# board.net
KiCad netlist of a schematic drawn in EAGLE
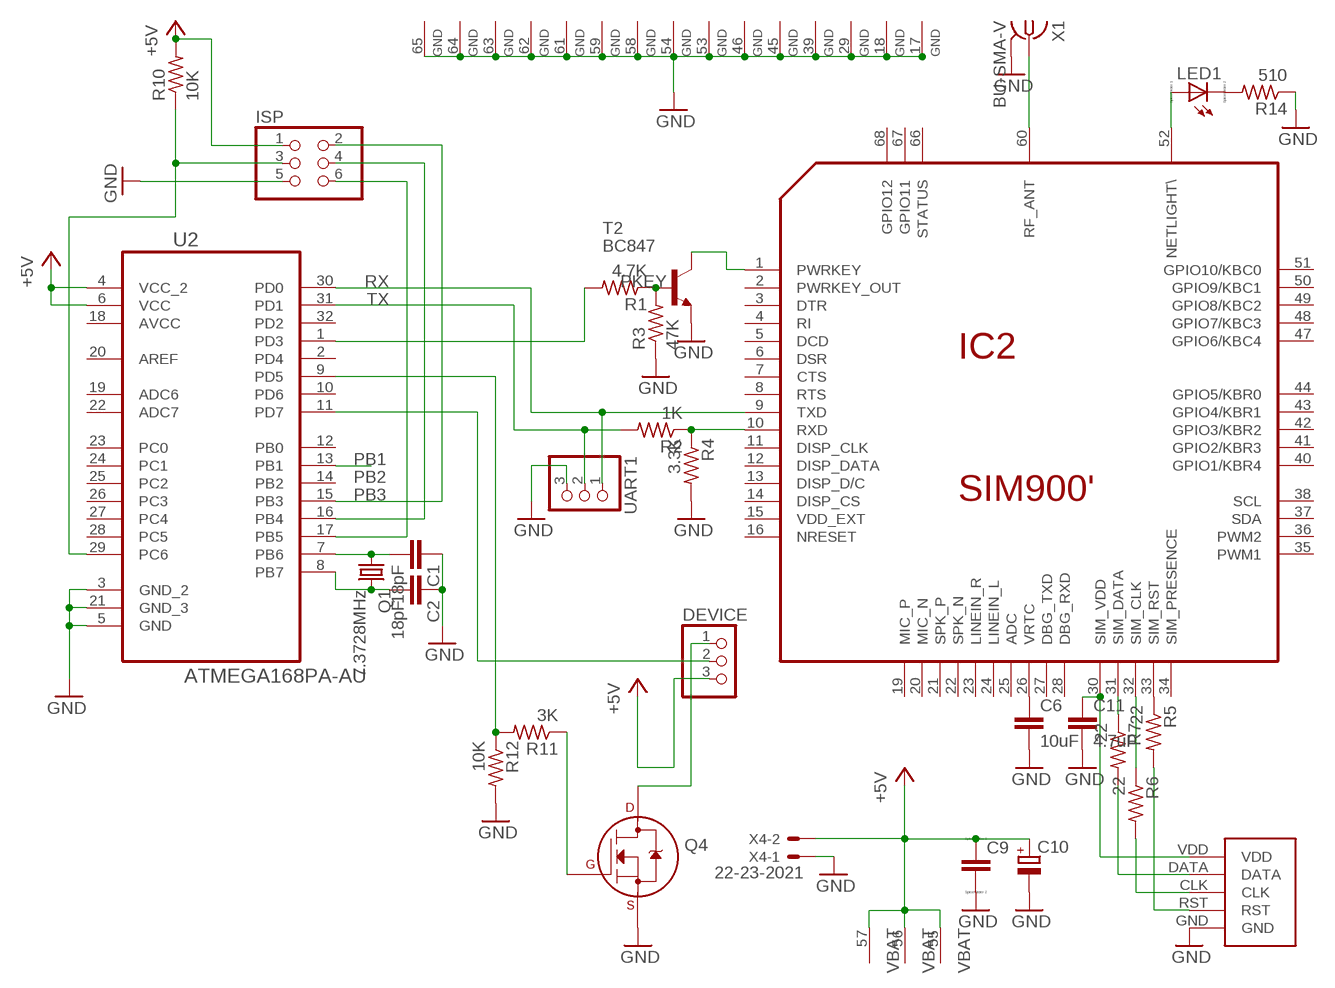
[diagram p0: schematic, sheet 1]

(export (version "E")
  (design (tool "Eeschema 10.0.6"))
  (components
    (comp (ref "C1")
      (value "18pF")
      (footprint "eagle-import:C1206")
      (libsource (lib "eagle-import") (part "C-EUC1206"))
    )
    (comp (ref "C2")
      (value "18pF")
      (footprint "eagle-import:C1206")
      (libsource (lib "eagle-import") (part "C-EUC1206"))
    )
    (comp (ref "C6")
      (value "10uF")
      (footprint "eagle-import:C1206")
      (libsource (lib "eagle-import") (part "C-EUC1206"))
    )
    (comp (ref "C9")
      (value "C-EUC1206K")
      (footprint "eagle-import:C1206K")
      (libsource (lib "eagle-import") (part "resistor_C-EUC1206K"))
    )
    (comp (ref "C10")
      (value "CPOL-EUE5-8.5")
      (footprint "eagle-import:E5-8,5")
      (libsource (lib "eagle-import") (part "CPOL-EUE5-8.5"))
    )
    (comp (ref "C11")
      (value "4.7uF")
      (footprint "eagle-import:C1206")
      (libsource (lib "eagle-import") (part "C-EUC1206"))
    )
    (comp (ref "DEVICE")
      (value "PINHD-1X3")
      (footprint "eagle-import:1X03")
      (libsource (lib "eagle-import") (part "PINHD-1X3"))
    )
    (comp (ref "IC2")
      (value "SIM900'")
      (footprint "eagle-import:SIM900_NARROW")
      (libsource (lib "eagle-import") (part "SIM900'"))
    )
    (comp (ref "ISP")
      (value "PINHD-2X3")
      (footprint "eagle-import:2X03")
      (libsource (lib "eagle-import") (part "PINHD-2X3"))
    )
    (comp (ref "LED1")
      (value "LED_E")
      (footprint "eagle-import:LED_1206")
      (libsource (lib "eagle-import") (part "LED_E"))
    )
    (comp (ref "Q1")
      (value "7.3728MHz")
      (footprint "eagle-import:HC49U-V")
      (libsource (lib "eagle-import") (part "CRYSTALHC49U-V"))
    )
    (comp (ref "Q4")
      (value "2N700_SOT23_1")
      (footprint "eagle-import:SOT23")
      (libsource (lib "eagle-import") (part "2N700_SOT23_1"))
    )
    (comp (ref "R1")
      (value "4.7K")
      (footprint "eagle-import:R1206")
      (libsource (lib "eagle-import") (part "R-US_R1206"))
    )
    (comp (ref "R2")
      (value "1K")
      (footprint "eagle-import:R1206")
      (libsource (lib "eagle-import") (part "R-US_R1206"))
    )
    (comp (ref "R3")
      (value "47K")
      (footprint "eagle-import:R1206")
      (libsource (lib "eagle-import") (part "R-US_R1206"))
    )
    (comp (ref "R4")
      (value "3.3K")
      (footprint "eagle-import:R1206")
      (libsource (lib "eagle-import") (part "R-US_R1206"))
    )
    (comp (ref "R5")
      (value "22")
      (footprint "eagle-import:R1206")
      (libsource (lib "eagle-import") (part "R-US_R1206"))
    )
    (comp (ref "R6")
      (value "22")
      (footprint "eagle-import:R1206")
      (libsource (lib "eagle-import") (part "R-US_R1206"))
    )
    (comp (ref "R7")
      (value "22")
      (footprint "eagle-import:R1206")
      (libsource (lib "eagle-import") (part "R-US_R1206"))
    )
    (comp (ref "R10")
      (value "10K")
      (footprint "eagle-import:M1206")
      (libsource (lib "eagle-import") (part "R-US_M1206"))
    )
    (comp (ref "R11")
      (value "3K")
      (footprint "eagle-import:M1206")
      (libsource (lib "eagle-import") (part "R-US_M1206"))
    )
    (comp (ref "R12")
      (value "10K")
      (footprint "eagle-import:M1206")
      (libsource (lib "eagle-import") (part "R-US_M1206"))
    )
    (comp (ref "R14")
      (value "510")
      (footprint "eagle-import:R1206")
      (libsource (lib "eagle-import") (part "R-US_R1206"))
    )
    (comp (ref "SIM_HOLDER")
      (value "115B-AAA0-R")
      (footprint "eagle-import:C707_10M006_512_2")
      (libsource (lib "eagle-import") (part "115B-AAA0-R"))
    )
    (comp (ref "T2")
      (value "BC847")
      (footprint "eagle-import:SOT23")
      (libsource (lib "eagle-import") (part "BC847"))
    )
    (comp (ref "U2")
      (value "ATMEGA168PA-AU")
      (footprint "eagle-import:QFP80P900X900X120-32N")
      (libsource (lib "eagle-import") (part "ATMEGA168PA-AU"))
    )
    (comp (ref "UART1")
      (value "PINHD-1X3")
      (footprint "eagle-import:1X03")
      (libsource (lib "eagle-import") (part "PINHD-1X3"))
    )
    (comp (ref "X1")
      (value "BU-SMA-V")
      (footprint "eagle-import:BU-SMA-V")
      (libsource (lib "eagle-import") (part "BU-SMA-V"))
    )
    (comp (ref "X4")
      (value "22-23-2021")
      (footprint "eagle-import:22-23-2021")
      (fields (field (name "MF") "MOLEX"))
      (libsource (lib "eagle-import") (part "22-23-2021"))
    )
  )
  (nets
    (net (code "1") (name "+5V") (class "Default")
      (node (ref "C10") (pin "+") (pinfunction "+_+") (pintype "passive"))
      (node (ref "C9") (pin "1") (pinfunction "1_1") (pintype "passive"))
      (node (ref "DEVICE") (pin "3") (pinfunction "3_3") (pintype "passive"))
      (node (ref "IC2") (pin "55") (pinfunction "VBAT_55") (pintype "power_in"))
      (node (ref "IC2") (pin "56") (pinfunction "VBAT_56") (pintype "power_in"))
      (node (ref "IC2") (pin "57") (pinfunction "VBAT_57") (pintype "power_in"))
      (node (ref "ISP") (pin "1") (pinfunction "1_1") (pintype "passive"))
      (node (ref "R10") (pin "2") (pinfunction "2_2") (pintype "passive"))
      (node (ref "U2") (pin "4") (pinfunction "VCC_2_4") (pintype "power_in"))
      (node (ref "U2") (pin "6") (pinfunction "VCC_6") (pintype "power_in"))
      (node (ref "X4") (pin "2") (pinfunction "S_2") (pintype "passive"))
    )
    (net (code "2") (name "/AVCC") (class "Default")
      (node (ref "U2") (pin "18") (pinfunction "AVCC_18") (pintype "power_in"))
    )
    (net (code "3") (name "/PB1") (class "Default")
      (node (ref "U2") (pin "13") (pinfunction "PB1_13") (pintype "bidirectional"))
    )
    (net (code "4") (name "/PB2") (class "Default")
      (node (ref "R11") (pin "2") (pinfunction "2_2") (pintype "passive"))
      (node (ref "R12") (pin "1") (pinfunction "1_1") (pintype "passive"))
      (node (ref "U2") (pin "9") (pinfunction "PD5_9") (pintype "bidirectional"))
    )
    (net (code "5") (name "/PB3") (class "Default")
      (node (ref "ISP") (pin "2") (pinfunction "2_2") (pintype "passive"))
      (node (ref "U2") (pin "15") (pinfunction "PB3_15") (pintype "bidirectional"))
    )
    (net (code "6") (name "/PKEY") (class "Default")
      (node (ref "R1") (pin "2") (pinfunction "2_2") (pintype "passive"))
      (node (ref "U2") (pin "1") (pinfunction "PD3_1") (pintype "bidirectional"))
    )
    (net (code "7") (name "/RX") (class "Default")
      (node (ref "IC2") (pin "9") (pinfunction "TXD_9") (pintype "bidirectional"))
      (node (ref "U2") (pin "30") (pinfunction "PD0_30") (pintype "bidirectional"))
      (node (ref "UART1") (pin "1") (pinfunction "1_1") (pintype "passive"))
    )
    (net (code "8") (name "/TX") (class "Default")
      (node (ref "R2") (pin "2") (pinfunction "2_2") (pintype "passive"))
      (node (ref "U2") (pin "31") (pinfunction "PD1_31") (pintype "bidirectional"))
      (node (ref "UART1") (pin "2") (pinfunction "2_2") (pintype "passive"))
    )
    (net (code "9") (name "GND") (class "Default")
      (node (ref "C1") (pin "1") (pinfunction "1_1") (pintype "passive"))
      (node (ref "C10") (pin "-") (pinfunction "-_-") (pintype "passive"))
      (node (ref "C11") (pin "2") (pinfunction "2_2") (pintype "passive"))
      (node (ref "C2") (pin "1") (pinfunction "1_1") (pintype "passive"))
      (node (ref "C6") (pin "2") (pinfunction "2_2") (pintype "passive"))
      (node (ref "C9") (pin "2") (pinfunction "2_2") (pintype "passive"))
      (node (ref "IC2") (pin "17") (pinfunction "GND_17") (pintype "power_in"))
      (node (ref "IC2") (pin "18") (pinfunction "GND_18") (pintype "power_in"))
      (node (ref "IC2") (pin "29") (pinfunction "GND_29") (pintype "power_in"))
      (node (ref "IC2") (pin "39") (pinfunction "GND_39") (pintype "power_in"))
      (node (ref "IC2") (pin "45") (pinfunction "GND_45") (pintype "power_in"))
      (node (ref "IC2") (pin "46") (pinfunction "GND_46") (pintype "power_in"))
      (node (ref "IC2") (pin "53") (pinfunction "GND_53") (pintype "power_in"))
      (node (ref "IC2") (pin "54") (pinfunction "GND_54") (pintype "power_in"))
      (node (ref "IC2") (pin "58") (pinfunction "GND_58") (pintype "power_in"))
      (node (ref "IC2") (pin "59") (pinfunction "GND_59") (pintype "power_in"))
      (node (ref "IC2") (pin "61") (pinfunction "GND_61") (pintype "power_in"))
      (node (ref "IC2") (pin "62") (pinfunction "GND_62") (pintype "power_in"))
      (node (ref "IC2") (pin "63") (pinfunction "GND_63") (pintype "power_in"))
      (node (ref "IC2") (pin "64") (pinfunction "GND_64") (pintype "power_in"))
      (node (ref "IC2") (pin "65") (pinfunction "GND_65") (pintype "power_in"))
      (node (ref "ISP") (pin "5") (pinfunction "5_5") (pintype "passive"))
      (node (ref "Q4") (pin "2") (pinfunction "S_2") (pintype "bidirectional"))
      (node (ref "R12") (pin "2") (pinfunction "2_2") (pintype "passive"))
      (node (ref "R14") (pin "1") (pinfunction "1_1") (pintype "passive"))
      (node (ref "R3") (pin "1") (pinfunction "1_1") (pintype "passive"))
      (node (ref "R4") (pin "2") (pinfunction "2_2") (pintype "passive"))
      (node (ref "SIM_HOLDER") (pin "GND") (pinfunction "GND_GND") (pintype "bidirectional"))
      (node (ref "T2") (pin "2") (pinfunction "E_2") (pintype "passive"))
      (node (ref "U2") (pin "21") (pinfunction "GND_3_21") (pintype "passive"))
      (node (ref "U2") (pin "3") (pinfunction "GND_2_3") (pintype "passive"))
      (node (ref "U2") (pin "5") (pinfunction "GND_5") (pintype "passive"))
      (node (ref "UART1") (pin "3") (pinfunction "3_3") (pintype "passive"))
      (node (ref "X1") (pin "2") (pinfunction "2_2") (pintype "passive"))
      (node (ref "X1") (pin "3") (pinfunction "2_3") (pintype "passive"))
      (node (ref "X1") (pin "4") (pinfunction "2_4") (pintype "passive"))
      (node (ref "X1") (pin "5") (pinfunction "2_5") (pintype "passive"))
      (node (ref "X4") (pin "1") (pinfunction "S_1") (pintype "passive"))
    )
    (net (code "10") (name "Net-(IC2A-NETLIGHT\\)") (class "Default")
      (node (ref "IC2") (pin "52") (pinfunction "NETLIGHT\\_52") (pintype "bidirectional"))
      (node (ref "LED1") (pin "A") (pinfunction "A_A") (pintype "passive"))
    )
    (net (code "11") (name "Net-(IC2A-PWRKEY)") (class "Default")
      (node (ref "IC2") (pin "1") (pinfunction "PWRKEY_1") (pintype "bidirectional"))
      (node (ref "T2") (pin "3") (pinfunction "C_3") (pintype "passive"))
    )
    (net (code "12") (name "Net-(IC2A-RF_ANT)") (class "Default")
      (node (ref "IC2") (pin "60") (pinfunction "RF_ANT_60") (pintype "bidirectional"))
      (node (ref "X1") (pin "1") (pinfunction "1_1") (pintype "passive"))
    )
    (net (code "13") (name "Net-(IC2A-RXD)") (class "Default")
      (node (ref "IC2") (pin "10") (pinfunction "RXD_10") (pintype "bidirectional"))
      (node (ref "R2") (pin "1") (pinfunction "1_1") (pintype "passive"))
      (node (ref "R4") (pin "1") (pinfunction "1_1") (pintype "passive"))
    )
    (net (code "14") (name "Net-(IC2A-SIM_CLK)") (class "Default")
      (node (ref "IC2") (pin "32") (pinfunction "SIM_CLK_32") (pintype "bidirectional"))
      (node (ref "R6") (pin "1") (pinfunction "1_1") (pintype "passive"))
    )
    (net (code "15") (name "Net-(IC2A-SIM_DATA)") (class "Default")
      (node (ref "IC2") (pin "31") (pinfunction "SIM_DATA_31") (pintype "bidirectional"))
      (node (ref "R7") (pin "1") (pinfunction "1_1") (pintype "passive"))
    )
    (net (code "16") (name "Net-(IC2A-SIM_RST)") (class "Default")
      (node (ref "IC2") (pin "33") (pinfunction "SIM_RST_33") (pintype "bidirectional"))
      (node (ref "R5") (pin "1") (pinfunction "1_1") (pintype "passive"))
    )
    (net (code "17") (name "Net-(IC2A-SIM_VDD)") (class "Default")
      (node (ref "C11") (pin "1") (pinfunction "1_1") (pintype "passive"))
      (node (ref "IC2") (pin "30") (pinfunction "SIM_VDD_30") (pintype "bidirectional"))
      (node (ref "SIM_HOLDER") (pin "VDD") (pinfunction "VDD_VDD") (pintype "bidirectional"))
    )
    (net (code "18") (name "Net-(IC2A-VRTC)") (class "Default")
      (node (ref "C6") (pin "1") (pinfunction "1_1") (pintype "passive"))
      (node (ref "IC2") (pin "26") (pinfunction "VRTC_26") (pintype "bidirectional"))
    )
    (net (code "19") (name "Net-(LED1-PadC)") (class "Default")
      (node (ref "LED1") (pin "C") (pinfunction "C_C") (pintype "passive"))
      (node (ref "R14") (pin "2") (pinfunction "2_2") (pintype "passive"))
    )
    (net (code "20") (name "Net-(Q4-D)") (class "Default")
      (node (ref "DEVICE") (pin "1") (pinfunction "1_1") (pintype "passive"))
      (node (ref "Q4") (pin "3") (pinfunction "D_3") (pintype "bidirectional"))
    )
    (net (code "21") (name "Net-(Q4-G)") (class "Default")
      (node (ref "Q4") (pin "1") (pinfunction "G_1") (pintype "tri_state"))
      (node (ref "R11") (pin "1") (pinfunction "1_1") (pintype "passive"))
    )
    (net (code "22") (name "Net-(R5-Pad2)") (class "Default")
      (node (ref "R5") (pin "2") (pinfunction "2_2") (pintype "passive"))
      (node (ref "SIM_HOLDER") (pin "RST") (pinfunction "RST_RST") (pintype "bidirectional"))
    )
    (net (code "23") (name "Net-(R6-Pad2)") (class "Default")
      (node (ref "R6") (pin "2") (pinfunction "2_2") (pintype "passive"))
      (node (ref "SIM_HOLDER") (pin "CLK") (pinfunction "CLK_CLK") (pintype "bidirectional"))
    )
    (net (code "24") (name "Net-(R7-Pad2)") (class "Default")
      (node (ref "R7") (pin "2") (pinfunction "2_2") (pintype "passive"))
      (node (ref "SIM_HOLDER") (pin "DATA") (pinfunction "DATA_DATA") (pintype "bidirectional"))
    )
    (net (code "25") (name "Net-(T2-B)") (class "Default")
      (node (ref "R1") (pin "1") (pinfunction "1_1") (pintype "passive"))
      (node (ref "R3") (pin "2") (pinfunction "2_2") (pintype "passive"))
      (node (ref "T2") (pin "1") (pinfunction "B_1") (pintype "passive"))
    )
    (net (code "26") (name "Net-(U2-PB4)") (class "Default")
      (node (ref "ISP") (pin "4") (pinfunction "4_4") (pintype "passive"))
      (node (ref "U2") (pin "16") (pinfunction "PB4_16") (pintype "bidirectional"))
    )
    (net (code "27") (name "Net-(U2-PB5)") (class "Default")
      (node (ref "ISP") (pin "6") (pinfunction "6_6") (pintype "passive"))
      (node (ref "U2") (pin "17") (pinfunction "PB5_17") (pintype "bidirectional"))
    )
    (net (code "28") (name "Net-(U2-PB6)") (class "Default")
      (node (ref "C1") (pin "2") (pinfunction "2_2") (pintype "passive"))
      (node (ref "Q1") (pin "1") (pinfunction "1_1") (pintype "passive"))
      (node (ref "U2") (pin "7") (pinfunction "PB6_7") (pintype "bidirectional"))
    )
    (net (code "29") (name "Net-(U2-PB7)") (class "Default")
      (node (ref "C2") (pin "2") (pinfunction "2_2") (pintype "passive"))
      (node (ref "Q1") (pin "2") (pinfunction "2_2") (pintype "passive"))
      (node (ref "U2") (pin "8") (pinfunction "PB7_8") (pintype "bidirectional"))
    )
    (net (code "30") (name "Net-(U2-PC6)") (class "Default")
      (node (ref "ISP") (pin "3") (pinfunction "3_3") (pintype "passive"))
      (node (ref "R10") (pin "1") (pinfunction "1_1") (pintype "passive"))
      (node (ref "U2") (pin "29") (pinfunction "PC6_29") (pintype "bidirectional"))
    )
    (net (code "31") (name "Net-(U2-PD7)") (class "Default")
      (node (ref "DEVICE") (pin "2") (pinfunction "2_2") (pintype "passive"))
      (node (ref "U2") (pin "11") (pinfunction "PD7_11") (pintype "bidirectional"))
    )
    (net (code "32") (name "unconnected-(IC2A-ADC-Pad25)") (class "Default")
      (node (ref "IC2") (pin "25") (pinfunction "ADC_25") (pintype "bidirectional"))
    )
    (net (code "33") (name "unconnected-(IC2A-CTS-Pad7)") (class "Default")
      (node (ref "IC2") (pin "7") (pinfunction "CTS_7") (pintype "bidirectional"))
    )
    (net (code "34") (name "unconnected-(IC2A-DBG_RXD-Pad28)") (class "Default")
      (node (ref "IC2") (pin "28") (pinfunction "DBG_RXD_28") (pintype "bidirectional"))
    )
    (net (code "35") (name "unconnected-(IC2A-DBG_TXD-Pad27)") (class "Default")
      (node (ref "IC2") (pin "27") (pinfunction "DBG_TXD_27") (pintype "bidirectional"))
    )
    (net (code "36") (name "unconnected-(IC2A-DCD-Pad5)") (class "Default")
      (node (ref "IC2") (pin "5") (pinfunction "DCD_5") (pintype "bidirectional"))
    )
    (net (code "37") (name "unconnected-(IC2A-DISP_CLK-Pad11)") (class "Default")
      (node (ref "IC2") (pin "11") (pinfunction "DISP_CLK_11") (pintype "bidirectional"))
    )
    (net (code "38") (name "unconnected-(IC2A-DISP_CS-Pad14)") (class "Default")
      (node (ref "IC2") (pin "14") (pinfunction "DISP_CS_14") (pintype "bidirectional"))
    )
    (net (code "39") (name "unconnected-(IC2A-DISP_DATA-Pad12)") (class "Default")
      (node (ref "IC2") (pin "12") (pinfunction "DISP_DATA_12") (pintype "bidirectional"))
    )
    (net (code "40") (name "unconnected-(IC2A-DISP_D{slash}C-Pad13)") (class "Default")
      (node (ref "IC2") (pin "13") (pinfunction "DISP_D/C_13") (pintype "bidirectional"))
    )
    (net (code "41") (name "unconnected-(IC2A-DSR-Pad6)") (class "Default")
      (node (ref "IC2") (pin "6") (pinfunction "DSR_6") (pintype "bidirectional"))
    )
    (net (code "42") (name "unconnected-(IC2A-DTR-Pad3)") (class "Default")
      (node (ref "IC2") (pin "3") (pinfunction "DTR_3") (pintype "bidirectional"))
    )
    (net (code "43") (name "unconnected-(IC2A-GPIO1{slash}KBR4-Pad40)") (class "Default")
      (node (ref "IC2") (pin "40") (pinfunction "GPIO1/KBR4_40") (pintype "bidirectional"))
    )
    (net (code "44") (name "unconnected-(IC2A-GPIO2{slash}KBR3-Pad41)") (class "Default")
      (node (ref "IC2") (pin "41") (pinfunction "GPIO2/KBR3_41") (pintype "bidirectional"))
    )
    (net (code "45") (name "unconnected-(IC2A-GPIO3{slash}KBR2-Pad42)") (class "Default")
      (node (ref "IC2") (pin "42") (pinfunction "GPIO3/KBR2_42") (pintype "bidirectional"))
    )
    (net (code "46") (name "unconnected-(IC2A-GPIO4{slash}KBR1-Pad43)") (class "Default")
      (node (ref "IC2") (pin "43") (pinfunction "GPIO4/KBR1_43") (pintype "bidirectional"))
    )
    (net (code "47") (name "unconnected-(IC2A-GPIO5{slash}KBR0-Pad44)") (class "Default")
      (node (ref "IC2") (pin "44") (pinfunction "GPIO5/KBR0_44") (pintype "bidirectional"))
    )
    (net (code "48") (name "unconnected-(IC2A-GPIO6{slash}KBC4-Pad47)") (class "Default")
      (node (ref "IC2") (pin "47") (pinfunction "GPIO6/KBC4_47") (pintype "bidirectional"))
    )
    (net (code "49") (name "unconnected-(IC2A-GPIO7{slash}KBC3-Pad48)") (class "Default")
      (node (ref "IC2") (pin "48") (pinfunction "GPIO7/KBC3_48") (pintype "bidirectional"))
    )
    (net (code "50") (name "unconnected-(IC2A-GPIO8{slash}KBC2-Pad49)") (class "Default")
      (node (ref "IC2") (pin "49") (pinfunction "GPIO8/KBC2_49") (pintype "bidirectional"))
    )
    (net (code "51") (name "unconnected-(IC2A-GPIO9{slash}KBC1-Pad50)") (class "Default")
      (node (ref "IC2") (pin "50") (pinfunction "GPIO9/KBC1_50") (pintype "bidirectional"))
    )
    (net (code "52") (name "unconnected-(IC2A-GPIO10{slash}KBC0-Pad51)") (class "Default")
      (node (ref "IC2") (pin "51") (pinfunction "GPIO10/KBC0_51") (pintype "bidirectional"))
    )
    (net (code "53") (name "unconnected-(IC2A-GPIO11-Pad67)") (class "Default")
      (node (ref "IC2") (pin "67") (pinfunction "GPIO11_67") (pintype "bidirectional"))
    )
    (net (code "54") (name "unconnected-(IC2A-GPIO12-Pad68)") (class "Default")
      (node (ref "IC2") (pin "68") (pinfunction "GPIO12_68") (pintype "bidirectional"))
    )
    (net (code "55") (name "unconnected-(IC2A-LINEIN_L-Pad24)") (class "Default")
      (node (ref "IC2") (pin "24") (pinfunction "LINEIN_L_24") (pintype "bidirectional"))
    )
    (net (code "56") (name "unconnected-(IC2A-LINEIN_R-Pad23)") (class "Default")
      (node (ref "IC2") (pin "23") (pinfunction "LINEIN_R_23") (pintype "bidirectional"))
    )
    (net (code "57") (name "unconnected-(IC2A-MIC_N-Pad20)") (class "Default")
      (node (ref "IC2") (pin "20") (pinfunction "MIC_N_20") (pintype "bidirectional"))
    )
    (net (code "58") (name "unconnected-(IC2A-MIC_P-Pad19)") (class "Default")
      (node (ref "IC2") (pin "19") (pinfunction "MIC_P_19") (pintype "bidirectional"))
    )
    (net (code "59") (name "unconnected-(IC2A-NRESET-Pad16)") (class "Default")
      (node (ref "IC2") (pin "16") (pinfunction "NRESET_16") (pintype "bidirectional"))
    )
    (net (code "60") (name "unconnected-(IC2A-PWM1-Pad35)") (class "Default")
      (node (ref "IC2") (pin "35") (pinfunction "PWM1_35") (pintype "bidirectional"))
    )
    (net (code "61") (name "unconnected-(IC2A-PWM2-Pad36)") (class "Default")
      (node (ref "IC2") (pin "36") (pinfunction "PWM2_36") (pintype "bidirectional"))
    )
    (net (code "62") (name "unconnected-(IC2A-PWRKEY_OUT-Pad2)") (class "Default")
      (node (ref "IC2") (pin "2") (pinfunction "PWRKEY_OUT_2") (pintype "bidirectional"))
    )
    (net (code "63") (name "unconnected-(IC2A-RI-Pad4)") (class "Default")
      (node (ref "IC2") (pin "4") (pinfunction "RI_4") (pintype "bidirectional"))
    )
    (net (code "64") (name "unconnected-(IC2A-RTS-Pad8)") (class "Default")
      (node (ref "IC2") (pin "8") (pinfunction "RTS_8") (pintype "bidirectional"))
    )
    (net (code "65") (name "unconnected-(IC2A-SCL-Pad38)") (class "Default")
      (node (ref "IC2") (pin "38") (pinfunction "SCL_38") (pintype "bidirectional"))
    )
    (net (code "66") (name "unconnected-(IC2A-SDA-Pad37)") (class "Default")
      (node (ref "IC2") (pin "37") (pinfunction "SDA_37") (pintype "bidirectional"))
    )
    (net (code "67") (name "unconnected-(IC2A-SIM_PRESENCE-Pad34)") (class "Default")
      (node (ref "IC2") (pin "34") (pinfunction "SIM_PRESENCE_34") (pintype "bidirectional"))
    )
    (net (code "68") (name "unconnected-(IC2A-SPK_N-Pad22)") (class "Default")
      (node (ref "IC2") (pin "22") (pinfunction "SPK_N_22") (pintype "bidirectional"))
    )
    (net (code "69") (name "unconnected-(IC2A-SPK_P-Pad21)") (class "Default")
      (node (ref "IC2") (pin "21") (pinfunction "SPK_P_21") (pintype "bidirectional"))
    )
    (net (code "70") (name "unconnected-(IC2A-STATUS-Pad66)") (class "Default")
      (node (ref "IC2") (pin "66") (pinfunction "STATUS_66") (pintype "bidirectional"))
    )
    (net (code "71") (name "unconnected-(IC2A-VDD_EXT-Pad15)") (class "Default")
      (node (ref "IC2") (pin "15") (pinfunction "VDD_EXT_15") (pintype "bidirectional"))
    )
    (net (code "72") (name "unconnected-(U2-ADC6-Pad19)") (class "Default")
      (node (ref "U2") (pin "19") (pinfunction "ADC6_19") (pintype "input"))
    )
    (net (code "73") (name "unconnected-(U2-ADC7-Pad22)") (class "Default")
      (node (ref "U2") (pin "22") (pinfunction "ADC7_22") (pintype "input"))
    )
    (net (code "74") (name "unconnected-(U2-AREF-Pad20)") (class "Default")
      (node (ref "U2") (pin "20") (pinfunction "AREF_20") (pintype "input"))
    )
    (net (code "75") (name "unconnected-(U2-PB0-Pad12)") (class "Default")
      (node (ref "U2") (pin "12") (pinfunction "PB0_12") (pintype "bidirectional"))
    )
    (net (code "76") (name "unconnected-(U2-PB2-Pad14)") (class "Default")
      (node (ref "U2") (pin "14") (pinfunction "PB2_14") (pintype "bidirectional"))
    )
    (net (code "77") (name "unconnected-(U2-PC0-Pad23)") (class "Default")
      (node (ref "U2") (pin "23") (pinfunction "PC0_23") (pintype "bidirectional"))
    )
    (net (code "78") (name "unconnected-(U2-PC1-Pad24)") (class "Default")
      (node (ref "U2") (pin "24") (pinfunction "PC1_24") (pintype "bidirectional"))
    )
    (net (code "79") (name "unconnected-(U2-PC2-Pad25)") (class "Default")
      (node (ref "U2") (pin "25") (pinfunction "PC2_25") (pintype "bidirectional"))
    )
    (net (code "80") (name "unconnected-(U2-PC3-Pad26)") (class "Default")
      (node (ref "U2") (pin "26") (pinfunction "PC3_26") (pintype "bidirectional"))
    )
    (net (code "81") (name "unconnected-(U2-PC4-Pad27)") (class "Default")
      (node (ref "U2") (pin "27") (pinfunction "PC4_27") (pintype "bidirectional"))
    )
    (net (code "82") (name "unconnected-(U2-PC5-Pad28)") (class "Default")
      (node (ref "U2") (pin "28") (pinfunction "PC5_28") (pintype "bidirectional"))
    )
    (net (code "83") (name "unconnected-(U2-PD2-Pad32)") (class "Default")
      (node (ref "U2") (pin "32") (pinfunction "PD2_32") (pintype "bidirectional"))
    )
    (net (code "84") (name "unconnected-(U2-PD4-Pad2)") (class "Default")
      (node (ref "U2") (pin "2") (pinfunction "PD4_2") (pintype "bidirectional"))
    )
    (net (code "85") (name "unconnected-(U2-PD6-Pad10)") (class "Default")
      (node (ref "U2") (pin "10") (pinfunction "PD6_10") (pintype "bidirectional"))
    )
  )
)
